# WEFT-encoder-demoboard.net
KiCad netlist of a schematic drawn in EAGLE
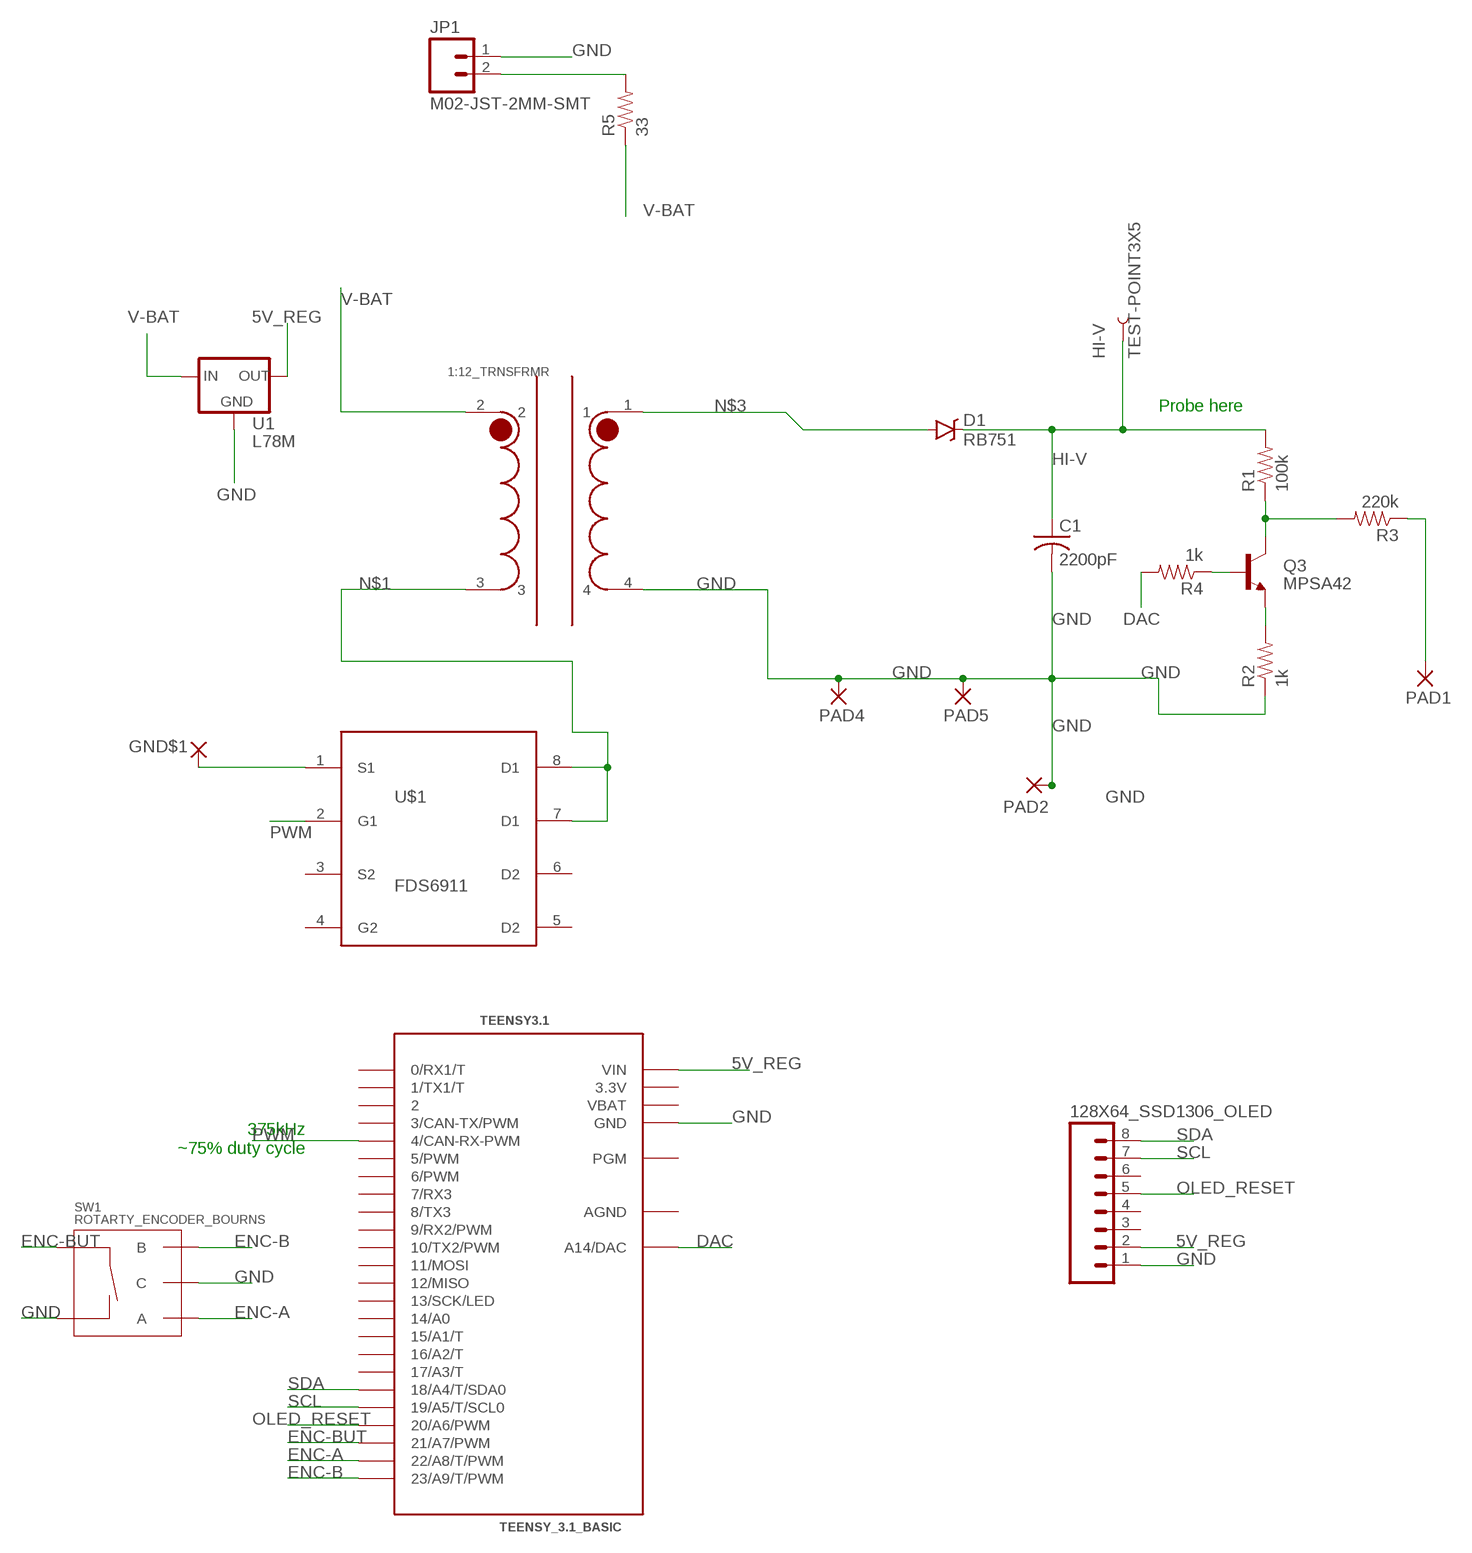
[diagram p0: schematic, sheet 1]

(export (version "E")
  (design (tool "Eeschema 10.0.6"))
  (components
    (comp (ref "1:12_TRNSFRMR")
      (value "PA0367")
      (footprint "eagle-import:PA0367")
      (libsource (lib "eagle-import") (part "PA0367"))
    )
    (comp (ref "128X64_SSD1306_OLED")
      (value "M08LOCK")
      (footprint "eagle-import:1X08_LOCK")
      (libsource (lib "eagle-import") (part "M08LOCK"))
    )
    (comp (ref "C1")
      (value "2200pF")
      (footprint "eagle-import:C1812")
      (libsource (lib "eagle-import") (part "C-USC1812"))
    )
    (comp (ref "D1")
      (value "RB751")
      (footprint "eagle-import:TO263")
      (libsource (lib "eagle-import") (part "QH03BZ600"))
    )
    (comp (ref "GND$1")
      (value "WIREPADSMD5-2,5")
      (footprint "eagle-import:5-2,5")
      (libsource (lib "eagle-import") (part "WIREPADSMD5-2,5"))
    )
    (comp (ref "HI-V")
      (value "TEST-POINT3X5")
      (footprint "eagle-import:PAD.03X.05")
      (libsource (lib "eagle-import") (part "TEST-POINT3X5"))
    )
    (comp (ref "JP1")
      (value "M02-JST-2MM-SMT")
      (footprint "eagle-import:JST-2-SMD")
      (libsource (lib "eagle-import") (part "M02-JST-2MM-SMT"))
    )
    (comp (ref "PAD1")
      (value "WIREPADSMD5-2,5")
      (footprint "eagle-import:5-2,5")
      (libsource (lib "eagle-import") (part "WIREPADSMD5-2,5"))
    )
    (comp (ref "PAD2")
      (value "WIREPADSMD5-2,5")
      (footprint "eagle-import:5-2,5")
      (libsource (lib "eagle-import") (part "WIREPADSMD5-2,5"))
    )
    (comp (ref "PAD4")
      (value "WIREPADSMD5-2,5")
      (footprint "eagle-import:5-2,5")
      (libsource (lib "eagle-import") (part "WIREPADSMD5-2,5"))
    )
    (comp (ref "PAD5")
      (value "WIREPADSMD5-2,5")
      (footprint "eagle-import:5-2,5")
      (libsource (lib "eagle-import") (part "WIREPADSMD5-2,5"))
    )
    (comp (ref "Q3")
      (value "MPSA42")
      (footprint "eagle-import:TO-92")
      (libsource (lib "eagle-import") (part "TRANSISTOR_NPNP2N2222A"))
    )
    (comp (ref "R1")
      (value "100k")
      (footprint "eagle-import:R2010")
      (libsource (lib "eagle-import") (part "RESISTOR2010"))
    )
    (comp (ref "R2")
      (value "1k")
      (footprint "eagle-import:1206")
      (libsource (lib "eagle-import") (part "RESISTOR1206"))
    )
    (comp (ref "R3")
      (value "220k")
      (footprint "eagle-import:R2010")
      (libsource (lib "eagle-import") (part "RESISTOR2010"))
    )
    (comp (ref "R4")
      (value "1k")
      (footprint "eagle-import:1206")
      (libsource (lib "eagle-import") (part "RESISTOR1206"))
    )
    (comp (ref "R5")
      (value "33")
      (footprint "eagle-import:1206")
      (libsource (lib "eagle-import") (part "RESISTOR1206"))
    )
    (comp (ref "SW1")
      (value "ROTARTY_ENCODER_BOURNS")
      (footprint "eagle-import:ROTARY_ENC_PLAIN_BOURNS")
      (libsource (lib "eagle-import") (part "ROTARTY_ENCODER_BOURNS"))
    )
    (comp (ref "TEENSY3.1")
      (value "TEENSY_3.1_BASIC")
      (footprint "eagle-import:TEENSY_3.1_BASIC")
      (libsource (lib "eagle-import") (part "TEENSY_3.1_BASIC"))
    )
    (comp (ref "U$1")
      (value "FDS6911")
      (footprint "eagle-import:SO8")
      (libsource (lib "eagle-import") (part "FDS6911"))
    )
    (comp (ref "U1")
      (value "L78M")
      (footprint "eagle-import:DPAK")
      (libsource (lib "eagle-import") (part "L78M"))
    )
  )
  (nets
    (net (code "1") (name "/3.3V") (class "Default")
      (node (ref "TEENSY3.1") (pin "3.3V") (pinfunction "3.3V_3.3V") (pintype "power_in"))
    )
    (net (code "2") (name "/5V_REG") (class "Default")
      (node (ref "128X64_SSD1306_OLED") (pin "2") (pinfunction "2_2") (pintype "passive"))
      (node (ref "TEENSY3.1") (pin "VIN") (pinfunction "VIN_VIN") (pintype "power_in"))
      (node (ref "U1") (pin "3") (pinfunction "OUT_3") (pintype "passive"))
    )
    (net (code "3") (name "/AGND") (class "Default")
      (node (ref "TEENSY3.1") (pin "AGND") (pinfunction "AGND_AGND") (pintype "power_in"))
    )
    (net (code "4") (name "/DAC") (class "Default")
      (node (ref "R4") (pin "2") (pinfunction "2_2") (pintype "passive"))
      (node (ref "TEENSY3.1") (pin "A14") (pinfunction "A14/DAC_A14") (pintype "bidirectional"))
    )
    (net (code "5") (name "/ENC-A") (class "Default")
      (node (ref "SW1") (pin "A") (pinfunction "A_A") (pintype "bidirectional"))
      (node (ref "TEENSY3.1") (pin "22/A8") (pinfunction "22/A8/T/PWM_22/A8") (pintype "bidirectional"))
    )
    (net (code "6") (name "/ENC-B") (class "Default")
      (node (ref "SW1") (pin "B") (pinfunction "B_B") (pintype "bidirectional"))
      (node (ref "TEENSY3.1") (pin "23/A9") (pinfunction "23/A9/T/PWM_23/A9") (pintype "bidirectional"))
    )
    (net (code "7") (name "/ENC-BUT") (class "Default")
      (node (ref "SW1") (pin "SW+") (pinfunction "SW+_SW+") (pintype "bidirectional"))
      (node (ref "TEENSY3.1") (pin "21/A7") (pinfunction "21/A7/PWM_21/A7") (pintype "bidirectional"))
    )
    (net (code "8") (name "/GND") (class "Default")
      (node (ref "128X64_SSD1306_OLED") (pin "1") (pinfunction "1_1") (pintype "passive"))
      (node (ref "1:12_TRNSFRMR") (pin "4") (pinfunction "4_4") (pintype "bidirectional"))
      (node (ref "C1") (pin "2") (pinfunction "2_2") (pintype "passive"))
      (node (ref "GND$1") (pin "1") (pinfunction "P_1") (pintype "passive"))
      (node (ref "JP1") (pin "1") (pinfunction "2_1") (pintype "passive"))
      (node (ref "PAD2") (pin "1") (pinfunction "P_1") (pintype "passive"))
      (node (ref "PAD4") (pin "1") (pinfunction "P_1") (pintype "passive"))
      (node (ref "PAD5") (pin "1") (pinfunction "P_1") (pintype "passive"))
      (node (ref "R2") (pin "1") (pinfunction "1_1") (pintype "passive"))
      (node (ref "SW1") (pin "C") (pinfunction "C_C") (pintype "bidirectional"))
      (node (ref "SW1") (pin "SW-") (pinfunction "SW-_SW-") (pintype "bidirectional"))
      (node (ref "TEENSY3.1") (pin "GND") (pinfunction "GND_GND") (pintype "power_in"))
      (node (ref "TEENSY3.1") (pin "GND1") (pinfunction "GND_GND1") (pintype "power_in"))
      (node (ref "U$1") (pin "1") (pinfunction "S1_1") (pintype "bidirectional"))
      (node (ref "U1") (pin "4") (pinfunction "GND_4") (pintype "input"))
    )
    (net (code "9") (name "/HI-V") (class "Default")
      (node (ref "C1") (pin "1") (pinfunction "1_1") (pintype "passive"))
      (node (ref "D1") (pin "1") (pinfunction "C_1") (pintype "passive"))
      (node (ref "HI-V") (pin "P$1") (pinfunction "1_P$1") (pintype "bidirectional"))
      (node (ref "R1") (pin "2") (pinfunction "2_2") (pintype "passive"))
    )
    (net (code "10") (name "/N$1") (class "Default")
      (node (ref "1:12_TRNSFRMR") (pin "3") (pinfunction "3_3") (pintype "bidirectional"))
      (node (ref "U$1") (pin "7") (pinfunction "D1_7") (pintype "bidirectional"))
      (node (ref "U$1") (pin "8") (pinfunction "D1_8") (pintype "bidirectional"))
    )
    (net (code "11") (name "/N$3") (class "Default")
      (node (ref "1:12_TRNSFRMR") (pin "1") (pinfunction "1_1") (pintype "bidirectional"))
      (node (ref "D1") (pin "2") (pinfunction "A_2") (pintype "passive"))
    )
    (net (code "12") (name "/OLED_RESET") (class "Default")
      (node (ref "128X64_SSD1306_OLED") (pin "5") (pinfunction "5_5") (pintype "passive"))
      (node (ref "TEENSY3.1") (pin "20/A6") (pinfunction "20/A6/PWM_20/A6") (pintype "bidirectional"))
    )
    (net (code "13") (name "/PWM") (class "Default")
      (node (ref "TEENSY3.1") (pin "4") (pinfunction "4/CAN-RX-PWM_4") (pintype "bidirectional"))
      (node (ref "U$1") (pin "2") (pinfunction "G1_2") (pintype "bidirectional"))
    )
    (net (code "14") (name "/SCL") (class "Default")
      (node (ref "128X64_SSD1306_OLED") (pin "7") (pinfunction "7_7") (pintype "passive"))
      (node (ref "TEENSY3.1") (pin "19/A5") (pinfunction "19/A5/T/SCL0_19/A5") (pintype "bidirectional"))
    )
    (net (code "15") (name "/SDA") (class "Default")
      (node (ref "128X64_SSD1306_OLED") (pin "8") (pinfunction "8_8") (pintype "passive"))
      (node (ref "TEENSY3.1") (pin "18/A4") (pinfunction "18/A4/T/SDA0_18/A4") (pintype "bidirectional"))
    )
    (net (code "16") (name "/V-BAT") (class "Default")
      (node (ref "1:12_TRNSFRMR") (pin "2") (pinfunction "2_2") (pintype "bidirectional"))
      (node (ref "R5") (pin "1") (pinfunction "1_1") (pintype "passive"))
      (node (ref "U1") (pin "1") (pinfunction "IN_1") (pintype "input"))
    )
    (net (code "17") (name "/VBAT") (class "Default")
      (node (ref "TEENSY3.1") (pin "VBAT") (pinfunction "VBAT_VBAT") (pintype "power_in"))
    )
    (net (code "18") (name "Net-(JP1-1)") (class "Default")
      (node (ref "JP1") (pin "2") (pinfunction "1_2") (pintype "passive"))
      (node (ref "R5") (pin "2") (pinfunction "2_2") (pintype "passive"))
    )
    (net (code "19") (name "Net-(PAD1-P)") (class "Default")
      (node (ref "PAD1") (pin "1") (pinfunction "P_1") (pintype "passive"))
      (node (ref "R3") (pin "1") (pinfunction "1_1") (pintype "passive"))
    )
    (net (code "20") (name "Net-(Q3-B)") (class "Default")
      (node (ref "Q3") (pin "2") (pinfunction "B_2") (pintype "passive"))
      (node (ref "R4") (pin "1") (pinfunction "1_1") (pintype "passive"))
    )
    (net (code "21") (name "Net-(Q3-C)") (class "Default")
      (node (ref "Q3") (pin "1") (pinfunction "C_1") (pintype "passive"))
      (node (ref "R1") (pin "1") (pinfunction "1_1") (pintype "passive"))
      (node (ref "R3") (pin "2") (pinfunction "2_2") (pintype "passive"))
    )
    (net (code "22") (name "Net-(Q3-E)") (class "Default")
      (node (ref "Q3") (pin "3") (pinfunction "E_3") (pintype "passive"))
      (node (ref "R2") (pin "2") (pinfunction "2_2") (pintype "passive"))
    )
    (net (code "23") (name "unconnected-(128X64_SSD1306_OLED-Pad3)") (class "Default")
      (node (ref "128X64_SSD1306_OLED") (pin "3") (pinfunction "3_3") (pintype "passive"))
    )
    (net (code "24") (name "unconnected-(128X64_SSD1306_OLED-Pad4)") (class "Default")
      (node (ref "128X64_SSD1306_OLED") (pin "4") (pinfunction "4_4") (pintype "passive"))
    )
    (net (code "25") (name "unconnected-(128X64_SSD1306_OLED-Pad6)") (class "Default")
      (node (ref "128X64_SSD1306_OLED") (pin "6") (pinfunction "6_6") (pintype "passive"))
    )
    (net (code "26") (name "unconnected-(TEENSY3.1-0{slash}RX1{slash}T-Pad0)") (class "Default")
      (node (ref "TEENSY3.1") (pin "0") (pinfunction "0/RX1/T_0") (pintype "bidirectional"))
    )
    (net (code "27") (name "unconnected-(TEENSY3.1-1{slash}TX1{slash}T-Pad1)") (class "Default")
      (node (ref "TEENSY3.1") (pin "1") (pinfunction "1/TX1/T_1") (pintype "bidirectional"))
    )
    (net (code "28") (name "unconnected-(TEENSY3.1-3{slash}CAN-TX{slash}PWM-Pad3)") (class "Default")
      (node (ref "TEENSY3.1") (pin "3") (pinfunction "3/CAN-TX/PWM_3") (pintype "bidirectional"))
    )
    (net (code "29") (name "unconnected-(TEENSY3.1-5{slash}PWM-Pad5)") (class "Default")
      (node (ref "TEENSY3.1") (pin "5") (pinfunction "5/PWM_5") (pintype "bidirectional"))
    )
    (net (code "30") (name "unconnected-(TEENSY3.1-6{slash}PWM-Pad6)") (class "Default")
      (node (ref "TEENSY3.1") (pin "6") (pinfunction "6/PWM_6") (pintype "bidirectional"))
    )
    (net (code "31") (name "unconnected-(TEENSY3.1-7{slash}RX3-Pad7)") (class "Default")
      (node (ref "TEENSY3.1") (pin "7") (pinfunction "7/RX3_7") (pintype "bidirectional"))
    )
    (net (code "32") (name "unconnected-(TEENSY3.1-8{slash}TX3-Pad8)") (class "Default")
      (node (ref "TEENSY3.1") (pin "8") (pinfunction "8/TX3_8") (pintype "bidirectional"))
    )
    (net (code "33") (name "unconnected-(TEENSY3.1-9{slash}RX2{slash}PWM-Pad9)") (class "Default")
      (node (ref "TEENSY3.1") (pin "9") (pinfunction "9/RX2/PWM_9") (pintype "bidirectional"))
    )
    (net (code "34") (name "unconnected-(TEENSY3.1-10{slash}TX2{slash}PWM-Pad10)") (class "Default")
      (node (ref "TEENSY3.1") (pin "10") (pinfunction "10/TX2/PWM_10") (pintype "bidirectional"))
    )
    (net (code "35") (name "unconnected-(TEENSY3.1-11{slash}MOSI-Pad11)") (class "Default")
      (node (ref "TEENSY3.1") (pin "11") (pinfunction "11/MOSI_11") (pintype "bidirectional"))
    )
    (net (code "36") (name "unconnected-(TEENSY3.1-12{slash}MISO-Pad12)") (class "Default")
      (node (ref "TEENSY3.1") (pin "12") (pinfunction "12/MISO_12") (pintype "bidirectional"))
    )
    (net (code "37") (name "unconnected-(TEENSY3.1-13{slash}SCK{slash}LED-Pad13)") (class "Default")
      (node (ref "TEENSY3.1") (pin "13") (pinfunction "13/SCK/LED_13") (pintype "bidirectional"))
    )
    (net (code "38") (name "unconnected-(TEENSY3.1-15{slash}A1{slash}T-Pad15{slash}A1)") (class "Default")
      (node (ref "TEENSY3.1") (pin "15/A1") (pinfunction "15/A1/T_15/A1") (pintype "bidirectional"))
    )
    (net (code "39") (name "unconnected-(TEENSY3.1-16{slash}A2{slash}T-Pad16{slash}A2)") (class "Default")
      (node (ref "TEENSY3.1") (pin "16/A2") (pinfunction "16/A2/T_16/A2") (pintype "bidirectional"))
    )
    (net (code "40") (name "unconnected-(TEENSY3.1-17{slash}A3{slash}T-Pad17{slash}A3)") (class "Default")
      (node (ref "TEENSY3.1") (pin "17/A3") (pinfunction "17/A3/T_17/A3") (pintype "bidirectional"))
    )
    (net (code "41") (name "unconnected-(TEENSY3.1-Pad2)") (class "Default")
      (node (ref "TEENSY3.1") (pin "2") (pinfunction "2_2") (pintype "bidirectional"))
    )
    (net (code "42") (name "unconnected-(TEENSY3.1-Pad14{slash}A0)") (class "Default")
      (node (ref "TEENSY3.1") (pin "14/A0") (pinfunction "14/A0_14/A0") (pintype "bidirectional"))
    )
    (net (code "43") (name "unconnected-(TEENSY3.1-PadPGM)") (class "Default")
      (node (ref "TEENSY3.1") (pin "PGM") (pinfunction "PGM_PGM") (pintype "bidirectional"))
    )
    (net (code "44") (name "unconnected-(U$1-D2-Pad5)") (class "Default")
      (node (ref "U$1") (pin "5") (pinfunction "D2_5") (pintype "bidirectional"))
    )
    (net (code "45") (name "unconnected-(U$1-D2-Pad6)") (class "Default")
      (node (ref "U$1") (pin "6") (pinfunction "D2_6") (pintype "bidirectional"))
    )
    (net (code "46") (name "unconnected-(U$1-G2-Pad4)") (class "Default")
      (node (ref "U$1") (pin "4") (pinfunction "G2_4") (pintype "bidirectional"))
    )
    (net (code "47") (name "unconnected-(U$1-S2-Pad3)") (class "Default")
      (node (ref "U$1") (pin "3") (pinfunction "S2_3") (pintype "bidirectional"))
    )
  )
)
